# downloader.net
KiCad netlist of a schematic drawn in Altium Designer
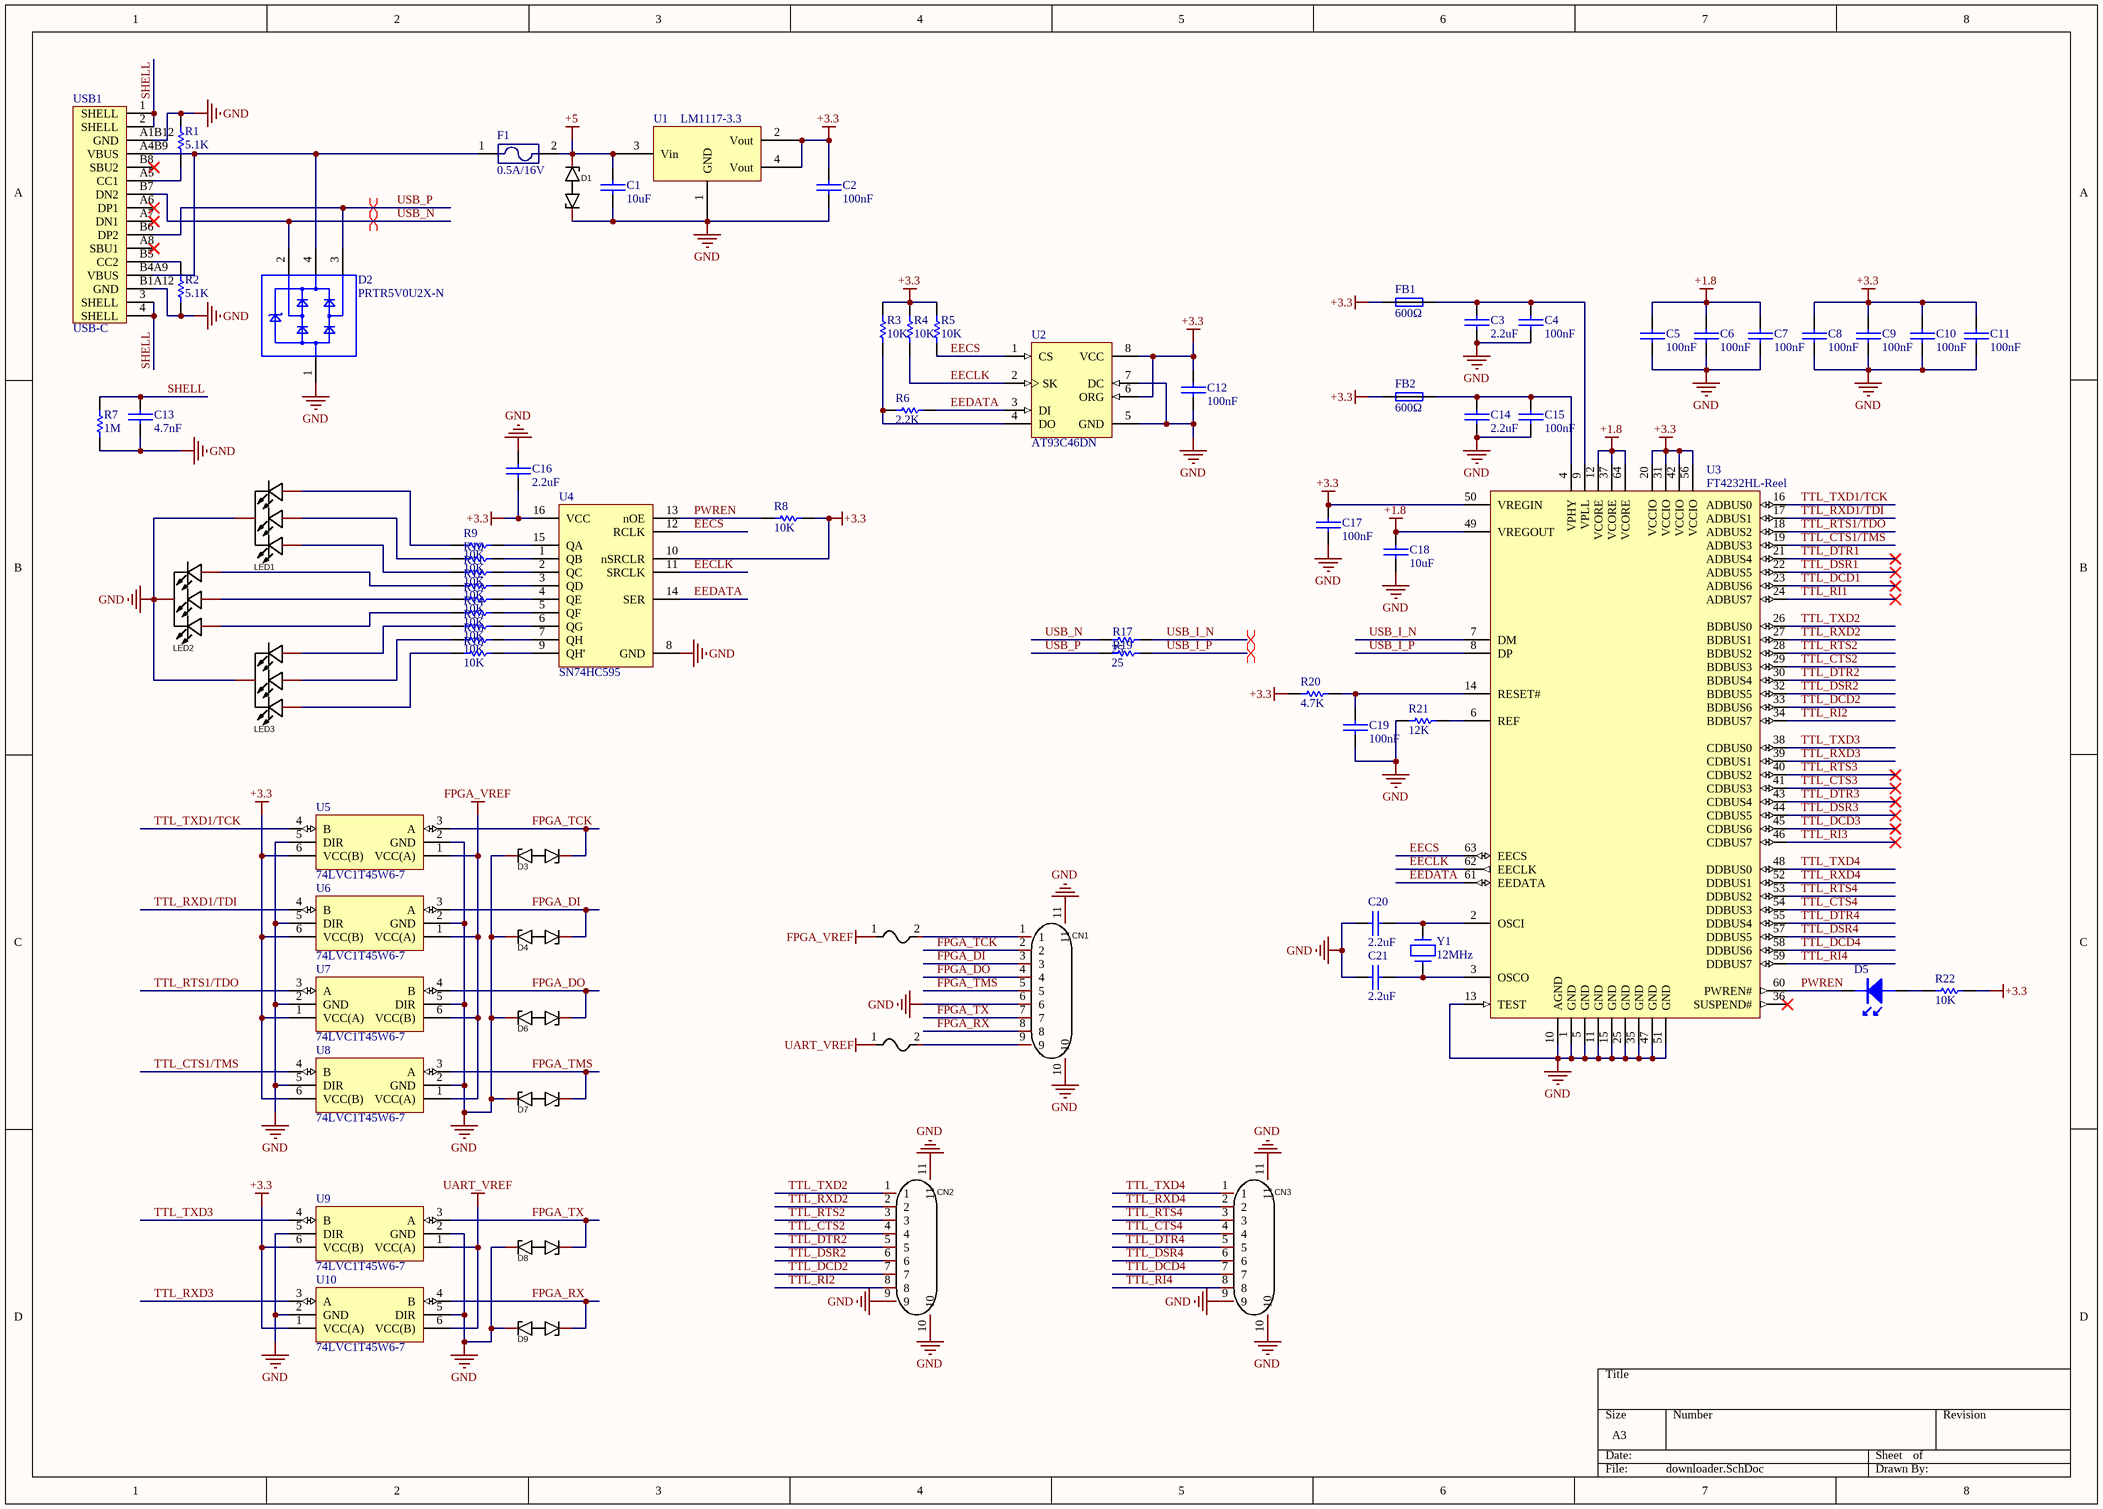
[diagram p0: downloader.SchDoc]

(export (version "E")
  (design (tool "Eeschema 10.0.6"))
  (components
    (comp (ref "C1") (value "10uF") (footprint "CAP-0603") (libsource (lib "downloader") (part "CAP0603")))
    (comp (ref "C2") (value "100nF") (footprint "CAP-0603") (libsource (lib "downloader") (part "CAP0603")))
    (comp (ref "C3") (value "2.2uF") (footprint "CAP-0603") (libsource (lib "downloader") (part "CAP0603")))
    (comp (ref "C4") (value "100nF") (footprint "CAP-0603") (libsource (lib "downloader") (part "CAP0603")))
    (comp (ref "C5") (value "100nF") (footprint "CAP-0603") (libsource (lib "downloader") (part "CAP0603")))
    (comp (ref "C6") (value "100nF") (footprint "CAP-0603") (libsource (lib "downloader") (part "CAP0603")))
    (comp (ref "C7") (value "100nF") (footprint "CAP-0603") (libsource (lib "downloader") (part "CAP0603")))
    (comp (ref "C8") (value "100nF") (footprint "CAP-0603") (libsource (lib "downloader") (part "CAP0603")))
    (comp (ref "C9") (value "100nF") (footprint "CAP-0603") (libsource (lib "downloader") (part "CAP0603")))
    (comp (ref "C10") (value "100nF") (footprint "CAP-0603") (libsource (lib "downloader") (part "CAP0603")))
    (comp (ref "C11") (value "100nF") (footprint "CAP-0603") (libsource (lib "downloader") (part "CAP0603")))
    (comp (ref "C12") (value "100nF") (footprint "CAP-0603") (libsource (lib "downloader") (part "CAP0603")))
    (comp (ref "C13") (value "4.7nF") (footprint "CAP-0603") (libsource (lib "downloader") (part "CAP-0603")))
    (comp (ref "C14") (value "2.2uF") (footprint "CAP-0603") (libsource (lib "downloader") (part "CAP0603")))
    (comp (ref "C15") (value "100nF") (footprint "CAP-0603") (libsource (lib "downloader") (part "CAP0603")))
    (comp (ref "C16") (value "2.2uF") (footprint "CAP-0603") (libsource (lib "downloader") (part "CAP-0603")))
    (comp (ref "C17") (value "100nF") (footprint "CAP-0603") (libsource (lib "downloader") (part "CAP0603")))
    (comp (ref "C18") (value "10uF") (footprint "CAP-0603") (libsource (lib "downloader") (part "CAP0603")))
    (comp (ref "C19") (value "100nF") (footprint "CAP-0603") (libsource (lib "downloader") (part "CAP-0603")))
    (comp (ref "C20") (value "2.2uF") (footprint "CAP-0603") (libsource (lib "downloader") (part "CAP-0603")))
    (comp (ref "C21") (value "2.2uF") (footprint "CAP-0603") (libsource (lib "downloader") (part "CAP-0603")))
    (comp (ref "CN1")
      (value "1.25-9PWT")
      (footprint "CONN-SMD_1.25-9PWT")
      (fields (field (name "MANUFACTURER") "FG(富港)"))
      (libsource (lib "downloader") (part "1.25-9PWT"))
    )
    (comp (ref "CN2")
      (value "1.25-9PWT")
      (footprint "CONN-SMD_1.25-9PWT")
      (fields (field (name "MANUFACTURER") "FG(富港)"))
      (libsource (lib "downloader") (part "1.25-9PWT"))
    )
    (comp (ref "CN3")
      (value "1.25-9PWT")
      (footprint "CONN-SMD_1.25-9PWT")
      (fields (field (name "MANUFACTURER") "FG(富港)"))
      (libsource (lib "downloader") (part "1.25-9PWT"))
    )
    (comp (ref "D1")
      (value "PESD5V0S1BA,115")
      (footprint "SOD-323")
      (description "115")
      (fields (field (name "MANUFACTURER") "Nexperia(安世)"))
      (libsource (lib "downloader") (part "PESD5V0S1BA"))
    )
    (comp (ref "D2")
      (value "PRTR5V0U2X-N")
      (footprint "SOT-143")
      (description "USB2.0-ESD")
      (libsource (lib "downloader") (part "PRTR5V0U2X-N"))
    )
    (comp (ref "D3")
      (value "PESD5V0S1BA,115")
      (footprint "SOD-323")
      (description "115")
      (fields (field (name "MANUFACTURER") "Nexperia(安世)"))
      (libsource (lib "downloader") (part "PESD5V0S1BA"))
    )
    (comp (ref "D4")
      (value "PESD5V0S1BA,115")
      (footprint "SOD-323")
      (description "115")
      (fields (field (name "MANUFACTURER") "Nexperia(安世)"))
      (libsource (lib "downloader") (part "PESD5V0S1BA"))
    )
    (comp (ref "D5") (value "~") (footprint "LED-0603") (libsource (lib "downloader") (part "LED-0603")))
    (comp (ref "D6")
      (value "PESD5V0S1BA,115")
      (footprint "SOD-323")
      (description "115")
      (fields (field (name "MANUFACTURER") "Nexperia(安世)"))
      (libsource (lib "downloader") (part "PESD5V0S1BA"))
    )
    (comp (ref "D7")
      (value "PESD5V0S1BA,115")
      (footprint "SOD-323")
      (description "115")
      (fields (field (name "MANUFACTURER") "Nexperia(安世)"))
      (libsource (lib "downloader") (part "PESD5V0S1BA"))
    )
    (comp (ref "D8")
      (value "PESD5V0S1BA,115")
      (footprint "SOD-323")
      (description "115")
      (fields (field (name "MANUFACTURER") "Nexperia(安世)"))
      (libsource (lib "downloader") (part "PESD5V0S1BA"))
    )
    (comp (ref "D9")
      (value "PESD5V0S1BA,115")
      (footprint "SOD-323")
      (description "115")
      (fields (field (name "MANUFACTURER") "Nexperia(安世)"))
      (libsource (lib "downloader") (part "PESD5V0S1BA"))
    )
    (comp (ref "F1") (value "0.5A/16V") (footprint "F-1206") (libsource (lib "downloader") (part "RE-FUSE")))
    (comp (ref "F2")
      (value "BSMD0805-050-6V")
      (footprint "F-0805")
      (description "050-6V")
      (fields (field (name "MANUFACTURER") "BHFUSE(佰宏)"))
      (libsource (lib "downloader") (part "BSMD0805"))
    )
    (comp (ref "F3")
      (value "BSMD0805-050-6V")
      (footprint "F-0805")
      (description "050-6V")
      (fields (field (name "MANUFACTURER") "BHFUSE(佰宏)"))
      (libsource (lib "downloader") (part "BSMD0805"))
    )
    (comp (ref "FB1") (value "600Ω") (footprint "FB-0603") (libsource (lib "downloader") (part "FB0603")))
    (comp (ref "FB2") (value "600Ω") (footprint "FB-0603") (libsource (lib "downloader") (part "FB0603")))
    (comp (ref "LED1")
      (value "TJ-S1615CY6TGLCCSRGB-A5")
      (footprint "LED-SMD_4P")
      (fields (field (name "MANUFACTURER") "TOGIALED(统佳)"))
      (libsource (lib "downloader") (part "TJ-S1615CY6TGLCCSRGB-A5"))
    )
    (comp (ref "LED2")
      (value "TJ-S1615CY6TGLCCSRGB-A5")
      (footprint "LED-SMD_4P")
      (fields (field (name "MANUFACTURER") "TOGIALED(统佳)"))
      (libsource (lib "downloader") (part "TJ-S1615CY6TGLCCSRGB-A5"))
    )
    (comp (ref "LED3")
      (value "TJ-S1615CY6TGLCCSRGB-A5")
      (footprint "LED-SMD_4P")
      (fields (field (name "MANUFACTURER") "TOGIALED(统佳)"))
      (libsource (lib "downloader") (part "TJ-S1615CY6TGLCCSRGB-A5"))
    )
    (comp (ref "R1") (value "5.1K") (footprint "RES-0603") (libsource (lib "downloader") (part "RES-0603")))
    (comp (ref "R2") (value "5.1K") (footprint "RES-0603") (libsource (lib "downloader") (part "RES-0603")))
    (comp (ref "R3") (value "10K") (footprint "RES-0603") (libsource (lib "downloader") (part "RES-0603")))
    (comp (ref "R4") (value "10K") (footprint "RES-0603") (libsource (lib "downloader") (part "RES-0603")))
    (comp (ref "R5") (value "10K") (footprint "RES-0603") (libsource (lib "downloader") (part "RES-0603")))
    (comp (ref "R6") (value "2.2K") (footprint "RES-0603") (libsource (lib "downloader") (part "RES-0603")))
    (comp (ref "R7") (value "1M") (footprint "RES-0603") (libsource (lib "downloader") (part "RES-0603")))
    (comp (ref "R8") (value "10K") (footprint "RES-0603") (libsource (lib "downloader") (part "RES-0603")))
    (comp (ref "R9") (value "10K") (footprint "RES-0603") (libsource (lib "downloader") (part "RES-0603")))
    (comp (ref "R10") (value "10K") (footprint "RES-0603") (libsource (lib "downloader") (part "RES-0603")))
    (comp (ref "R11") (value "10K") (footprint "RES-0603") (libsource (lib "downloader") (part "RES-0603")))
    (comp (ref "R12") (value "10K") (footprint "RES-0603") (libsource (lib "downloader") (part "RES-0603")))
    (comp (ref "R13") (value "10K") (footprint "RES-0603") (libsource (lib "downloader") (part "RES-0603")))
    (comp (ref "R14") (value "10K") (footprint "RES-0603") (libsource (lib "downloader") (part "RES-0603")))
    (comp (ref "R15") (value "10K") (footprint "RES-0603") (libsource (lib "downloader") (part "RES-0603")))
    (comp (ref "R16") (value "10K") (footprint "RES-0603") (libsource (lib "downloader") (part "RES-0603")))
    (comp (ref "R17") (value "25") (footprint "RES-0603") (libsource (lib "downloader") (part "RES-0603")))
    (comp (ref "R18") (value "10K") (footprint "RES-0603") (libsource (lib "downloader") (part "RES-0603")))
    (comp (ref "R19") (value "25") (footprint "RES-0603") (libsource (lib "downloader") (part "RES-0603")))
    (comp (ref "R20") (value "4.7K") (footprint "RES-0603") (libsource (lib "downloader") (part "RES-0603")))
    (comp (ref "R21") (value "12K") (footprint "RES-0603") (libsource (lib "downloader") (part "RES-0603")))
    (comp (ref "R22") (value "10K") (footprint "RES-0603") (libsource (lib "downloader") (part "RES-0603")))
    (comp (ref "U1")
      (value "LM1117-3.3")
      (footprint "SOT-223")
      (description "LDO")
      (libsource (lib "downloader") (part "LM1117-3.3"))
    )
    (comp (ref "U2") (value "AT93C46DN") (footprint "SO-8") (libsource (lib "downloader") (part "AT93C46DN")))
    (comp (ref "U3")
      (value "FT4232HL-Reel")
      (footprint "LQFP-64")
      (description "Quad High Speed USB To Multipurpose UART/MPSSE IC, LQFP-64, Tape and Reel")
      (fields (field (name "PUBLISHER") "Altium Limited"))
      (libsource (lib "downloader") (part "FT4232HL-Reel"))
    )
    (comp (ref "U4")
      (value "SN74HC595")
      (footprint "SO-16")
      (libsource (lib "downloader") (part "SN74HC595"))
    )
    (comp (ref "U5")
      (value "74LVC1T45W6-7")
      (footprint "SOT-23-6")
      (libsource (lib "downloader") (part "74LVC1T45W6-7"))
    )
    (comp (ref "U6")
      (value "74LVC1T45W6-7")
      (footprint "SOT-23-6")
      (libsource (lib "downloader") (part "74LVC1T45W6-7"))
    )
    (comp (ref "U7")
      (value "74LVC1T45W6-7")
      (footprint "SOT-23-6")
      (libsource (lib "") (part "74LVC1T45W6-7_1"))
    )
    (comp (ref "U8")
      (value "74LVC1T45W6-7")
      (footprint "SOT-23-6")
      (libsource (lib "downloader") (part "74LVC1T45W6-7"))
    )
    (comp (ref "U9")
      (value "74LVC1T45W6-7")
      (footprint "SOT-23-6")
      (libsource (lib "downloader") (part "74LVC1T45W6-7"))
    )
    (comp (ref "U10")
      (value "74LVC1T45W6-7")
      (footprint "SOT-23-6")
      (libsource (lib "") (part "74LVC1T45W6-7_1"))
    )
    (comp (ref "USB1")
      (value "USB-C")
      (footprint "USB-C")
      (description "16P")
      (libsource (lib "downloader") (part "USB-C-16P"))
    )
    (comp (ref "Y1")
      (value "12MHz")
      (footprint "XTAL-49/S_N")
      (libsource (lib "downloader") (part "XTAL-49/S_N"))
    )
  )
  (nets
    (net (code "1") (name "+1.8") (class "Default")
      (node (ref "C18") (pin "2") (pinfunction "2_2") (pintype "passive"))
      (node (ref "C5") (pin "2") (pinfunction "2_2") (pintype "passive"))
      (node (ref "C6") (pin "2") (pinfunction "2_2") (pintype "passive"))
      (node (ref "C7") (pin "2") (pinfunction "2_2") (pintype "passive"))
      (node (ref "U3") (pin "12") (pinfunction "VCORE_12") (pintype "power_in"))
      (node (ref "U3") (pin "37") (pinfunction "VCORE_37") (pintype "power_in"))
      (node (ref "U3") (pin "49") (pinfunction "VREGOUT_49") (pintype "power_in"))
      (node (ref "U3") (pin "64") (pinfunction "VCORE_64") (pintype "power_in"))
    )
    (net (code "2") (name "+3.3") (class "Default")
      (node (ref "C10") (pin "2") (pinfunction "2_2") (pintype "passive"))
      (node (ref "C11") (pin "2") (pinfunction "2_2") (pintype "passive"))
      (node (ref "C12") (pin "2") (pinfunction "2_2") (pintype "passive"))
      (node (ref "C16") (pin "2") (pinfunction "2_2") (pintype "passive"))
      (node (ref "C17") (pin "2") (pinfunction "2_2") (pintype "passive"))
      (node (ref "C2") (pin "2") (pinfunction "2_2") (pintype "passive"))
      (node (ref "C8") (pin "2") (pinfunction "2_2") (pintype "passive"))
      (node (ref "C9") (pin "2") (pinfunction "2_2") (pintype "passive"))
      (node (ref "FB1") (pin "1") (pinfunction "1_1") (pintype "passive"))
      (node (ref "FB2") (pin "1") (pinfunction "1_1") (pintype "passive"))
      (node (ref "R20") (pin "1") (pinfunction "1_1") (pintype "passive"))
      (node (ref "R22") (pin "2") (pinfunction "2_2") (pintype "passive"))
      (node (ref "R3") (pin "1") (pinfunction "1_1") (pintype "passive"))
      (node (ref "R4") (pin "1") (pinfunction "1_1") (pintype "passive"))
      (node (ref "R5") (pin "1") (pinfunction "1_1") (pintype "passive"))
      (node (ref "R8") (pin "2") (pinfunction "2_2") (pintype "passive"))
      (node (ref "U1") (pin "2") (pinfunction "Vout_2") (pintype "passive"))
      (node (ref "U1") (pin "4") (pinfunction "Vout_4") (pintype "passive"))
      (node (ref "U10") (pin "1") (pinfunction "VCC(A)_1") (pintype "power_in"))
      (node (ref "U2") (pin "6") (pinfunction "ORG_6") (pintype "input"))
      (node (ref "U2") (pin "8") (pinfunction "VCC_8") (pintype "power_in"))
      (node (ref "U3") (pin "20") (pinfunction "VCCIO_20") (pintype "power_in"))
      (node (ref "U3") (pin "31") (pinfunction "VCCIO_31") (pintype "power_in"))
      (node (ref "U3") (pin "42") (pinfunction "VCCIO_42") (pintype "power_in"))
      (node (ref "U3") (pin "50") (pinfunction "VREGIN_50") (pintype "power_in"))
      (node (ref "U3") (pin "56") (pinfunction "VCCIO_56") (pintype "power_in"))
      (node (ref "U4") (pin "10") (pinfunction "nSRCLR_10") (pintype "passive"))
      (node (ref "U4") (pin "16") (pinfunction "VCC_16") (pintype "passive"))
      (node (ref "U5") (pin "6") (pinfunction "VCC(B)_6") (pintype "power_in"))
      (node (ref "U6") (pin "6") (pinfunction "VCC(B)_6") (pintype "power_in"))
      (node (ref "U7") (pin "1") (pinfunction "VCC(A)_1") (pintype "power_in"))
      (node (ref "U8") (pin "6") (pinfunction "VCC(B)_6") (pintype "power_in"))
      (node (ref "U9") (pin "6") (pinfunction "VCC(B)_6") (pintype "power_in"))
    )
    (net (code "3") (name "+5") (class "Default")
      (node (ref "C1") (pin "2") (pinfunction "2_2") (pintype "passive"))
      (node (ref "D1") (pin "2") (pinfunction "2_2") (pintype "passive"))
      (node (ref "F1") (pin "2") (pinfunction "2_2") (pintype "passive"))
      (node (ref "U1") (pin "3") (pinfunction "Vin_3") (pintype "power_in"))
    )
    (net (code "4") (name "/EECLK") (class "Default")
      (node (ref "R4") (pin "2") (pinfunction "2_2") (pintype "passive"))
      (node (ref "U2") (pin "2") (pinfunction "SK_2") (pintype "input"))
      (node (ref "U3") (pin "62") (pinfunction "EECLK_62") (pintype "output"))
      (node (ref "U4") (pin "11") (pinfunction "SRCLK_11") (pintype "passive"))
    )
    (net (code "5") (name "/EECS") (class "Default")
      (node (ref "R5") (pin "2") (pinfunction "2_2") (pintype "passive"))
      (node (ref "U2") (pin "1") (pinfunction "CS_1") (pintype "input"))
      (node (ref "U3") (pin "63") (pinfunction "EECS_63") (pintype "bidirectional"))
      (node (ref "U4") (pin "12") (pinfunction "RCLK_12") (pintype "passive"))
    )
    (net (code "6") (name "/EEDATA") (class "Default")
      (node (ref "R6") (pin "2") (pinfunction "2_2") (pintype "passive"))
      (node (ref "U2") (pin "3") (pinfunction "DI_3") (pintype "input"))
      (node (ref "U3") (pin "61") (pinfunction "EEDATA_61") (pintype "bidirectional"))
      (node (ref "U4") (pin "14") (pinfunction "SER_14") (pintype "passive"))
    )
    (net (code "7") (name "/FPGA_DI") (class "Default")
      (node (ref "CN1") (pin "3") (pinfunction "3_3") (pintype "passive"))
      (node (ref "D4") (pin "2") (pinfunction "2_2") (pintype "passive"))
      (node (ref "U6") (pin "3") (pinfunction "A_3") (pintype "bidirectional"))
    )
    (net (code "8") (name "/FPGA_DO") (class "Default")
      (node (ref "CN1") (pin "4") (pinfunction "4_4") (pintype "passive"))
      (node (ref "D6") (pin "2") (pinfunction "2_2") (pintype "passive"))
      (node (ref "U7") (pin "4") (pinfunction "B_4") (pintype "bidirectional"))
    )
    (net (code "9") (name "/FPGA_RX") (class "Default")
      (node (ref "CN1") (pin "8") (pinfunction "8_8") (pintype "passive"))
      (node (ref "D9") (pin "2") (pinfunction "2_2") (pintype "passive"))
      (node (ref "U10") (pin "4") (pinfunction "B_4") (pintype "bidirectional"))
    )
    (net (code "10") (name "/FPGA_TCK") (class "Default")
      (node (ref "CN1") (pin "2") (pinfunction "2_2") (pintype "passive"))
      (node (ref "D3") (pin "2") (pinfunction "2_2") (pintype "passive"))
      (node (ref "U5") (pin "3") (pinfunction "A_3") (pintype "bidirectional"))
    )
    (net (code "11") (name "/FPGA_TMS") (class "Default")
      (node (ref "CN1") (pin "5") (pinfunction "5_5") (pintype "passive"))
      (node (ref "D7") (pin "2") (pinfunction "2_2") (pintype "passive"))
      (node (ref "U8") (pin "3") (pinfunction "A_3") (pintype "bidirectional"))
    )
    (net (code "12") (name "/FPGA_TX") (class "Default")
      (node (ref "CN1") (pin "7") (pinfunction "7_7") (pintype "passive"))
      (node (ref "D8") (pin "2") (pinfunction "2_2") (pintype "passive"))
      (node (ref "U9") (pin "3") (pinfunction "A_3") (pintype "bidirectional"))
    )
    (net (code "13") (name "/PWREN") (class "Default")
      (node (ref "D5") (pin "1") (pinfunction "1_1") (pintype "passive"))
      (node (ref "R8") (pin "1") (pinfunction "1_1") (pintype "passive"))
      (node (ref "U3") (pin "60") (pinfunction "PWREN#_60") (pintype "output"))
      (node (ref "U4") (pin "13") (pinfunction "nOE_13") (pintype "passive"))
    )
    (net (code "14") (name "/SHELL") (class "Default")
      (node (ref "C13") (pin "2") (pinfunction "2_2") (pintype "passive"))
      (node (ref "R7") (pin "2") (pinfunction "2_2") (pintype "passive"))
      (node (ref "USB1") (pin "1") (pinfunction "SHELL_1") (pintype "power_in"))
      (node (ref "USB1") (pin "2") (pinfunction "SHELL_2") (pintype "power_in"))
      (node (ref "USB1") (pin "3") (pinfunction "SHELL_3") (pintype "power_in"))
      (node (ref "USB1") (pin "4") (pinfunction "SHELL_4") (pintype "power_in"))
    )
    (net (code "15") (name "/TTL_CTS1{slash}TMS") (class "Default")
      (node (ref "U3") (pin "19") (pinfunction "ADBUS3_19") (pintype "bidirectional"))
      (node (ref "U8") (pin "4") (pinfunction "B_4") (pintype "bidirectional"))
    )
    (net (code "16") (name "/TTL_CTS2") (class "Default")
      (node (ref "CN2") (pin "4") (pinfunction "4_4") (pintype "passive"))
      (node (ref "U3") (pin "29") (pinfunction "BDBUS3_29") (pintype "bidirectional"))
    )
    (net (code "17") (name "/TTL_CTS3") (class "Default")
      (node (ref "U3") (pin "41") (pinfunction "CDBUS3_41") (pintype "bidirectional+no_connect"))
    )
    (net (code "18") (name "/TTL_CTS4") (class "Default")
      (node (ref "CN3") (pin "4") (pinfunction "4_4") (pintype "passive"))
      (node (ref "U3") (pin "54") (pinfunction "DDBUS3_54") (pintype "bidirectional"))
    )
    (net (code "19") (name "/TTL_DCD1") (class "Default")
      (node (ref "U3") (pin "23") (pinfunction "ADBUS6_23") (pintype "bidirectional+no_connect"))
    )
    (net (code "20") (name "/TTL_DCD2") (class "Default")
      (node (ref "CN2") (pin "7") (pinfunction "7_7") (pintype "passive"))
      (node (ref "U3") (pin "33") (pinfunction "BDBUS6_33") (pintype "bidirectional"))
    )
    (net (code "21") (name "/TTL_DCD3") (class "Default")
      (node (ref "U3") (pin "45") (pinfunction "CDBUS6_45") (pintype "bidirectional+no_connect"))
    )
    (net (code "22") (name "/TTL_DCD4") (class "Default")
      (node (ref "CN3") (pin "7") (pinfunction "7_7") (pintype "passive"))
      (node (ref "U3") (pin "58") (pinfunction "DDBUS6_58") (pintype "bidirectional"))
    )
    (net (code "23") (name "/TTL_DSR1") (class "Default")
      (node (ref "U3") (pin "22") (pinfunction "ADBUS5_22") (pintype "bidirectional+no_connect"))
    )
    (net (code "24") (name "/TTL_DSR2") (class "Default")
      (node (ref "CN2") (pin "6") (pinfunction "6_6") (pintype "passive"))
      (node (ref "U3") (pin "32") (pinfunction "BDBUS5_32") (pintype "bidirectional"))
    )
    (net (code "25") (name "/TTL_DSR3") (class "Default")
      (node (ref "U3") (pin "44") (pinfunction "CDBUS5_44") (pintype "bidirectional+no_connect"))
    )
    (net (code "26") (name "/TTL_DSR4") (class "Default")
      (node (ref "CN3") (pin "6") (pinfunction "6_6") (pintype "passive"))
      (node (ref "U3") (pin "57") (pinfunction "DDBUS5_57") (pintype "bidirectional"))
    )
    (net (code "27") (name "/TTL_DTR1") (class "Default")
      (node (ref "U3") (pin "21") (pinfunction "ADBUS4_21") (pintype "bidirectional+no_connect"))
    )
    (net (code "28") (name "/TTL_DTR2") (class "Default")
      (node (ref "CN2") (pin "5") (pinfunction "5_5") (pintype "passive"))
      (node (ref "U3") (pin "30") (pinfunction "BDBUS4_30") (pintype "bidirectional"))
    )
    (net (code "29") (name "/TTL_DTR3") (class "Default")
      (node (ref "U3") (pin "43") (pinfunction "CDBUS4_43") (pintype "bidirectional+no_connect"))
    )
    (net (code "30") (name "/TTL_DTR4") (class "Default")
      (node (ref "CN3") (pin "5") (pinfunction "5_5") (pintype "passive"))
      (node (ref "U3") (pin "55") (pinfunction "DDBUS4_55") (pintype "bidirectional"))
    )
    (net (code "31") (name "/TTL_RI1") (class "Default")
      (node (ref "U3") (pin "24") (pinfunction "ADBUS7_24") (pintype "bidirectional+no_connect"))
    )
    (net (code "32") (name "/TTL_RI2") (class "Default")
      (node (ref "CN2") (pin "8") (pinfunction "8_8") (pintype "passive"))
      (node (ref "U3") (pin "34") (pinfunction "BDBUS7_34") (pintype "bidirectional"))
    )
    (net (code "33") (name "/TTL_RI3") (class "Default")
      (node (ref "U3") (pin "46") (pinfunction "CDBUS7_46") (pintype "bidirectional+no_connect"))
    )
    (net (code "34") (name "/TTL_RI4") (class "Default")
      (node (ref "CN3") (pin "8") (pinfunction "8_8") (pintype "passive"))
      (node (ref "U3") (pin "59") (pinfunction "DDBUS7_59") (pintype "bidirectional"))
    )
    (net (code "35") (name "/TTL_RTS1{slash}TDO") (class "Default")
      (node (ref "U3") (pin "18") (pinfunction "ADBUS2_18") (pintype "bidirectional"))
      (node (ref "U7") (pin "3") (pinfunction "A_3") (pintype "bidirectional"))
    )
    (net (code "36") (name "/TTL_RTS2") (class "Default")
      (node (ref "CN2") (pin "3") (pinfunction "3_3") (pintype "passive"))
      (node (ref "U3") (pin "28") (pinfunction "BDBUS2_28") (pintype "bidirectional"))
    )
    (net (code "37") (name "/TTL_RTS3") (class "Default")
      (node (ref "U3") (pin "40") (pinfunction "CDBUS2_40") (pintype "bidirectional+no_connect"))
    )
    (net (code "38") (name "/TTL_RTS4") (class "Default")
      (node (ref "CN3") (pin "3") (pinfunction "3_3") (pintype "passive"))
      (node (ref "U3") (pin "53") (pinfunction "DDBUS2_53") (pintype "bidirectional"))
    )
    (net (code "39") (name "/TTL_RXD1{slash}TDI") (class "Default")
      (node (ref "U3") (pin "17") (pinfunction "ADBUS1_17") (pintype "bidirectional"))
      (node (ref "U6") (pin "4") (pinfunction "B_4") (pintype "bidirectional"))
    )
    (net (code "40") (name "/TTL_RXD2") (class "Default")
      (node (ref "CN2") (pin "2") (pinfunction "2_2") (pintype "passive"))
      (node (ref "U3") (pin "27") (pinfunction "BDBUS1_27") (pintype "bidirectional"))
    )
    (net (code "41") (name "/TTL_RXD3") (class "Default")
      (node (ref "U10") (pin "3") (pinfunction "A_3") (pintype "bidirectional"))
      (node (ref "U3") (pin "39") (pinfunction "CDBUS1_39") (pintype "bidirectional"))
    )
    (net (code "42") (name "/TTL_RXD4") (class "Default")
      (node (ref "CN3") (pin "2") (pinfunction "2_2") (pintype "passive"))
      (node (ref "U3") (pin "52") (pinfunction "DDBUS1_52") (pintype "bidirectional"))
    )
    (net (code "43") (name "/TTL_TXD1{slash}TCK") (class "Default")
      (node (ref "U3") (pin "16") (pinfunction "ADBUS0_16") (pintype "bidirectional"))
      (node (ref "U5") (pin "4") (pinfunction "B_4") (pintype "bidirectional"))
    )
    (net (code "44") (name "/TTL_TXD2") (class "Default")
      (node (ref "CN2") (pin "1") (pinfunction "1_1") (pintype "passive"))
      (node (ref "U3") (pin "26") (pinfunction "BDBUS0_26") (pintype "bidirectional"))
    )
    (net (code "45") (name "/TTL_TXD3") (class "Default")
      (node (ref "U3") (pin "38") (pinfunction "CDBUS0_38") (pintype "bidirectional"))
      (node (ref "U9") (pin "4") (pinfunction "B_4") (pintype "bidirectional"))
    )
    (net (code "46") (name "/TTL_TXD4") (class "Default")
      (node (ref "CN3") (pin "1") (pinfunction "1_1") (pintype "passive"))
      (node (ref "U3") (pin "48") (pinfunction "DDBUS0_48") (pintype "bidirectional"))
    )
    (net (code "47") (name "/USB_I_N") (class "Default")
      (node (ref "R17") (pin "2") (pinfunction "2_2") (pintype "passive"))
      (node (ref "U3") (pin "7") (pinfunction "DM_7") (pintype "passive"))
    )
    (net (code "48") (name "/USB_I_P") (class "Default")
      (node (ref "R19") (pin "2") (pinfunction "2_2") (pintype "passive"))
      (node (ref "U3") (pin "8") (pinfunction "DP_8") (pintype "passive"))
    )
    (net (code "49") (name "/USB_N") (class "Default")
      (node (ref "D2") (pin "2") (pinfunction "2_2") (pintype "passive"))
      (node (ref "R17") (pin "1") (pinfunction "1_1") (pintype "passive"))
      (node (ref "USB1") (pin "B7") (pinfunction "DN2_B7") (pintype "power_in"))
    )
    (net (code "50") (name "/USB_P") (class "Default")
      (node (ref "D2") (pin "3") (pinfunction "3_3") (pintype "passive"))
      (node (ref "R19") (pin "1") (pinfunction "1_1") (pintype "passive"))
      (node (ref "USB1") (pin "B6") (pinfunction "DP2_B6") (pintype "power_in"))
    )
    (net (code "51") (name "FPGA_VREF") (class "Default")
      (node (ref "F2") (pin "1") (pinfunction "1_1") (pintype "passive"))
      (node (ref "U5") (pin "1") (pinfunction "VCC(A)_1") (pintype "power_in"))
      (node (ref "U6") (pin "1") (pinfunction "VCC(A)_1") (pintype "power_in"))
      (node (ref "U7") (pin "6") (pinfunction "VCC(B)_6") (pintype "power_in"))
      (node (ref "U8") (pin "1") (pinfunction "VCC(A)_1") (pintype "power_in"))
    )
    (net (code "52") (name "GND") (class "Default")
      (node (ref "C1") (pin "1") (pinfunction "1_1") (pintype "passive"))
      (node (ref "C10") (pin "1") (pinfunction "1_1") (pintype "passive"))
      (node (ref "C11") (pin "1") (pinfunction "1_1") (pintype "passive"))
      (node (ref "C12") (pin "1") (pinfunction "1_1") (pintype "passive"))
      (node (ref "C13") (pin "1") (pinfunction "1_1") (pintype "passive"))
      (node (ref "C14") (pin "1") (pinfunction "1_1") (pintype "passive"))
      (node (ref "C15") (pin "1") (pinfunction "1_1") (pintype "passive"))
      (node (ref "C16") (pin "1") (pinfunction "1_1") (pintype "passive"))
      (node (ref "C17") (pin "1") (pinfunction "1_1") (pintype "passive"))
      (node (ref "C18") (pin "1") (pinfunction "1_1") (pintype "passive"))
      (node (ref "C19") (pin "1") (pinfunction "1_1") (pintype "passive"))
      (node (ref "C2") (pin "1") (pinfunction "1_1") (pintype "passive"))
      (node (ref "C20") (pin "1") (pinfunction "1_1") (pintype "passive"))
      (node (ref "C21") (pin "1") (pinfunction "1_1") (pintype "passive"))
      (node (ref "C3") (pin "1") (pinfunction "1_1") (pintype "passive"))
      (node (ref "C4") (pin "1") (pinfunction "1_1") (pintype "passive"))
      (node (ref "C5") (pin "1") (pinfunction "1_1") (pintype "passive"))
      (node (ref "C6") (pin "1") (pinfunction "1_1") (pintype "passive"))
      (node (ref "C7") (pin "1") (pinfunction "1_1") (pintype "passive"))
      (node (ref "C8") (pin "1") (pinfunction "1_1") (pintype "passive"))
      (node (ref "C9") (pin "1") (pinfunction "1_1") (pintype "passive"))
      (node (ref "CN1") (pin "10") (pinfunction "10_10") (pintype "passive"))
      (node (ref "CN1") (pin "11") (pinfunction "11_11") (pintype "passive"))
      (node (ref "CN1") (pin "6") (pinfunction "6_6") (pintype "passive"))
      (node (ref "CN2") (pin "10") (pinfunction "10_10") (pintype "passive"))
      (node (ref "CN2") (pin "11") (pinfunction "11_11") (pintype "passive"))
      (node (ref "CN2") (pin "9") (pinfunction "9_9") (pintype "passive"))
      (node (ref "CN3") (pin "10") (pinfunction "10_10") (pintype "passive"))
      (node (ref "CN3") (pin "11") (pinfunction "11_11") (pintype "passive"))
      (node (ref "CN3") (pin "9") (pinfunction "9_9") (pintype "passive"))
      (node (ref "D1") (pin "1") (pinfunction "1_1") (pintype "passive"))
      (node (ref "D2") (pin "1") (pinfunction "1_1") (pintype "passive"))
      (node (ref "D3") (pin "1") (pinfunction "1_1") (pintype "passive"))
      (node (ref "D4") (pin "1") (pinfunction "1_1") (pintype "passive"))
      (node (ref "D6") (pin "1") (pinfunction "1_1") (pintype "passive"))
      (node (ref "D7") (pin "1") (pinfunction "1_1") (pintype "passive"))
      (node (ref "D8") (pin "1") (pinfunction "1_1") (pintype "passive"))
      (node (ref "D9") (pin "1") (pinfunction "1_1") (pintype "passive"))
      (node (ref "LED1") (pin "1") (pinfunction "C_1") (pintype "passive"))
      (node (ref "LED2") (pin "1") (pinfunction "C_1") (pintype "passive"))
      (node (ref "LED3") (pin "1") (pinfunction "C_1") (pintype "passive"))
      (node (ref "R1") (pin "2") (pinfunction "2_2") (pintype "passive"))
      (node (ref "R2") (pin "1") (pinfunction "1_1") (pintype "passive"))
      (node (ref "R21") (pin "1") (pinfunction "1_1") (pintype "passive"))
      (node (ref "R7") (pin "1") (pinfunction "1_1") (pintype "passive"))
      (node (ref "U1") (pin "1") (pinfunction "GND_1") (pintype "passive"))
      (node (ref "U10") (pin "2") (pinfunction "GND_2") (pintype "power_in"))
      (node (ref "U10") (pin "5") (pinfunction "DIR_5") (pintype "power_in"))
      (node (ref "U2") (pin "5") (pinfunction "GND_5") (pintype "power_in"))
      (node (ref "U2") (pin "7") (pinfunction "DC_7") (pintype "input"))
      (node (ref "U3") (pin "1") (pinfunction "GND_1") (pintype "power_in"))
      (node (ref "U3") (pin "10") (pinfunction "AGND_10") (pintype "power_in"))
      (node (ref "U3") (pin "11") (pinfunction "GND_11") (pintype "power_in"))
      (node (ref "U3") (pin "13") (pinfunction "TEST_13") (pintype "input"))
      (node (ref "U3") (pin "15") (pinfunction "GND_15") (pintype "power_in"))
      (node (ref "U3") (pin "25") (pinfunction "GND_25") (pintype "power_in"))
      (node (ref "U3") (pin "35") (pinfunction "GND_35") (pintype "power_in"))
      (node (ref "U3") (pin "47") (pinfunction "GND_47") (pintype "power_in"))
      (node (ref "U3") (pin "5") (pinfunction "GND_5") (pintype "power_in"))
      (node (ref "U3") (pin "51") (pinfunction "GND_51") (pintype "power_in"))
      (node (ref "U4") (pin "8") (pinfunction "GND_8") (pintype "passive"))
      (node (ref "U5") (pin "2") (pinfunction "GND_2") (pintype "power_in"))
      (node (ref "U5") (pin "5") (pinfunction "DIR_5") (pintype "power_in"))
      (node (ref "U6") (pin "2") (pinfunction "GND_2") (pintype "power_in"))
      (node (ref "U6") (pin "5") (pinfunction "DIR_5") (pintype "power_in"))
      (node (ref "U7") (pin "2") (pinfunction "GND_2") (pintype "power_in"))
      (node (ref "U7") (pin "5") (pinfunction "DIR_5") (pintype "power_in"))
      (node (ref "U8") (pin "2") (pinfunction "GND_2") (pintype "power_in"))
      (node (ref "U8") (pin "5") (pinfunction "DIR_5") (pintype "power_in"))
      (node (ref "U9") (pin "2") (pinfunction "GND_2") (pintype "power_in"))
      (node (ref "U9") (pin "5") (pinfunction "DIR_5") (pintype "power_in"))
      (node (ref "USB1") (pin "A1B12") (pinfunction "GND_A1B12") (pintype "power_in"))
      (node (ref "USB1") (pin "B1A12") (pinfunction "GND_B1A12") (pintype "power_in"))
    )
    (net (code "53") (name "Net-(CN1-Pad1)") (class "Default")
      (node (ref "CN1") (pin "1") (pinfunction "1_1") (pintype "passive"))
      (node (ref "F2") (pin "2") (pinfunction "2_2") (pintype "passive"))
    )
    (net (code "54") (name "Net-(CN1-Pad9)") (class "Default")
      (node (ref "CN1") (pin "9") (pinfunction "9_9") (pintype "passive"))
      (node (ref "F3") (pin "2") (pinfunction "2_2") (pintype "passive"))
    )
    (net (code "55") (name "Net-(D2-Pad4)") (class "Default")
      (node (ref "D2") (pin "4") (pinfunction "4_4") (pintype "passive"))
      (node (ref "F1") (pin "1") (pinfunction "1_1") (pintype "passive"))
      (node (ref "USB1") (pin "A4B9") (pinfunction "VBUS_A4B9") (pintype "power_in"))
      (node (ref "USB1") (pin "B4A9") (pinfunction "VBUS_B4A9") (pintype "power_in"))
    )
    (net (code "56") (name "Net-(D5-Pad2)") (class "Default")
      (node (ref "D5") (pin "2") (pinfunction "2_2") (pintype "passive"))
      (node (ref "R22") (pin "1") (pinfunction "1_1") (pintype "passive"))
    )
    (net (code "57") (name "Net-(LED1-B)") (class "Default")
      (node (ref "LED1") (pin "2") (pinfunction "B_2") (pintype "passive"))
      (node (ref "R11") (pin "1") (pinfunction "1_1") (pintype "passive"))
    )
    (net (code "58") (name "Net-(LED1-G)") (class "Default")
      (node (ref "LED1") (pin "3") (pinfunction "G_3") (pintype "passive"))
      (node (ref "R10") (pin "1") (pinfunction "1_1") (pintype "passive"))
    )
    (net (code "59") (name "Net-(LED1-R)") (class "Default")
      (node (ref "LED1") (pin "4") (pinfunction "R_4") (pintype "passive"))
      (node (ref "R9") (pin "1") (pinfunction "1_1") (pintype "passive"))
    )
    (net (code "60") (name "Net-(LED2-B)") (class "Default")
      (node (ref "LED2") (pin "2") (pinfunction "B_2") (pintype "passive"))
      (node (ref "R14") (pin "1") (pinfunction "1_1") (pintype "passive"))
    )
    (net (code "61") (name "Net-(LED2-G)") (class "Default")
      (node (ref "LED2") (pin "3") (pinfunction "G_3") (pintype "passive"))
      (node (ref "R13") (pin "1") (pinfunction "1_1") (pintype "passive"))
    )
    (net (code "62") (name "Net-(LED2-R)") (class "Default")
      (node (ref "LED2") (pin "4") (pinfunction "R_4") (pintype "passive"))
      (node (ref "R12") (pin "1") (pinfunction "1_1") (pintype "passive"))
    )
    (net (code "63") (name "Net-(LED3-B)") (class "Default")
      (node (ref "LED3") (pin "2") (pinfunction "B_2") (pintype "passive"))
      (node (ref "R18") (pin "1") (pinfunction "1_1") (pintype "passive"))
    )
    (net (code "64") (name "Net-(LED3-G)") (class "Default")
      (node (ref "LED3") (pin "3") (pinfunction "G_3") (pintype "passive"))
      (node (ref "R16") (pin "1") (pinfunction "1_1") (pintype "passive"))
    )
    (net (code "65") (name "Net-(LED3-R)") (class "Default")
      (node (ref "LED3") (pin "4") (pinfunction "R_4") (pintype "passive"))
      (node (ref "R15") (pin "1") (pinfunction "1_1") (pintype "passive"))
    )
    (net (code "66") (name "Net-(U2-DO)") (class "Default")
      (node (ref "R3") (pin "2") (pinfunction "2_2") (pintype "passive"))
      (node (ref "R6") (pin "1") (pinfunction "1_1") (pintype "passive"))
      (node (ref "U2") (pin "4") (pinfunction "DO_4") (pintype "tri_state"))
    )
    (net (code "67") (name "Net-(U3-OSCI)") (class "Default")
      (node (ref "C20") (pin "2") (pinfunction "2_2") (pintype "passive"))
      (node (ref "U3") (pin "2") (pinfunction "OSCI_2") (pintype "passive"))
      (node (ref "Y1") (pin "2") (pinfunction "2_2") (pintype "passive"))
    )
    (net (code "68") (name "Net-(U3-OSCO)") (class "Default")
      (node (ref "C21") (pin "2") (pinfunction "2_2") (pintype "passive"))
      (node (ref "U3") (pin "3") (pinfunction "OSCO_3") (pintype "passive"))
      (node (ref "Y1") (pin "1") (pinfunction "1_1") (pintype "passive"))
    )
    (net (code "69") (name "Net-(U3-REF)") (class "Default")
      (node (ref "R21") (pin "2") (pinfunction "2_2") (pintype "passive"))
      (node (ref "U3") (pin "6") (pinfunction "REF_6") (pintype "passive"))
    )
    (net (code "70") (name "Net-(U3-RESET#)") (class "Default")
      (node (ref "C19") (pin "2") (pinfunction "2_2") (pintype "passive"))
      (node (ref "R20") (pin "2") (pinfunction "2_2") (pintype "passive"))
      (node (ref "U3") (pin "14") (pinfunction "RESET#_14") (pintype "passive"))
    )
    (net (code "71") (name "Net-(U3-VPHY)") (class "Default")
      (node (ref "C14") (pin "2") (pinfunction "2_2") (pintype "passive"))
      (node (ref "C15") (pin "2") (pinfunction "2_2") (pintype "passive"))
      (node (ref "FB2") (pin "2") (pinfunction "2_2") (pintype "passive"))
      (node (ref "U3") (pin "4") (pinfunction "VPHY_4") (pintype "power_in"))
    )
    (net (code "72") (name "Net-(U3-VPLL)") (class "Default")
      (node (ref "C3") (pin "2") (pinfunction "2_2") (pintype "passive"))
      (node (ref "C4") (pin "2") (pinfunction "2_2") (pintype "passive"))
      (node (ref "FB1") (pin "2") (pinfunction "2_2") (pintype "passive"))
      (node (ref "U3") (pin "9") (pinfunction "VPLL_9") (pintype "power_in"))
    )
    (net (code "73") (name "Net-(U4-QA)") (class "Default")
      (node (ref "R9") (pin "2") (pinfunction "2_2") (pintype "passive"))
      (node (ref "U4") (pin "15") (pinfunction "QA_15") (pintype "passive"))
    )
    (net (code "74") (name "Net-(U4-QB)") (class "Default")
      (node (ref "R10") (pin "2") (pinfunction "2_2") (pintype "passive"))
      (node (ref "U4") (pin "1") (pinfunction "QB_1") (pintype "passive"))
    )
    (net (code "75") (name "Net-(U4-QC)") (class "Default")
      (node (ref "R11") (pin "2") (pinfunction "2_2") (pintype "passive"))
      (node (ref "U4") (pin "2") (pinfunction "QC_2") (pintype "passive"))
    )
    (net (code "76") (name "Net-(U4-QD)") (class "Default")
      (node (ref "R12") (pin "2") (pinfunction "2_2") (pintype "passive"))
      (node (ref "U4") (pin "3") (pinfunction "QD_3") (pintype "passive"))
    )
    (net (code "77") (name "Net-(U4-QE)") (class "Default")
      (node (ref "R13") (pin "2") (pinfunction "2_2") (pintype "passive"))
      (node (ref "U4") (pin "4") (pinfunction "QE_4") (pintype "passive"))
    )
    (net (code "78") (name "Net-(U4-QF)") (class "Default")
      (node (ref "R14") (pin "2") (pinfunction "2_2") (pintype "passive"))
      (node (ref "U4") (pin "5") (pinfunction "QF_5") (pintype "passive"))
    )
    (net (code "79") (name "Net-(U4-QG)") (class "Default")
      (node (ref "R15") (pin "2") (pinfunction "2_2") (pintype "passive"))
      (node (ref "U4") (pin "6") (pinfunction "QG_6") (pintype "passive"))
    )
    (net (code "80") (name "Net-(U4-QH')") (class "Default")
      (node (ref "R18") (pin "2") (pinfunction "2_2") (pintype "passive"))
      (node (ref "U4") (pin "9") (pinfunction "QH'_9") (pintype "passive"))
    )
    (net (code "81") (name "Net-(U4-QH)") (class "Default")
      (node (ref "R16") (pin "2") (pinfunction "2_2") (pintype "passive"))
      (node (ref "U4") (pin "7") (pinfunction "QH_7") (pintype "passive"))
    )
    (net (code "82") (name "Net-(USB1-CC1)") (class "Default")
      (node (ref "R1") (pin "1") (pinfunction "1_1") (pintype "passive"))
      (node (ref "USB1") (pin "A5") (pinfunction "CC1_A5") (pintype "power_in"))
    )
    (net (code "83") (name "Net-(USB1-CC2)") (class "Default")
      (node (ref "R2") (pin "2") (pinfunction "2_2") (pintype "passive"))
      (node (ref "USB1") (pin "B5") (pinfunction "CC2_B5") (pintype "power_in"))
    )
    (net (code "84") (name "UART_VREF") (class "Default")
      (node (ref "F3") (pin "1") (pinfunction "1_1") (pintype "passive"))
      (node (ref "U10") (pin "6") (pinfunction "VCC(B)_6") (pintype "power_in"))
      (node (ref "U9") (pin "1") (pinfunction "VCC(A)_1") (pintype "power_in"))
    )
    (net (code "85") (name "unconnected-(U3-SUSPEND#-Pad36)") (class "Default")
      (node (ref "U3") (pin "36") (pinfunction "SUSPEND#_36") (pintype "output+no_connect"))
    )
    (net (code "86") (name "unconnected-(USB1-DN1-PadA7)") (class "Default")
      (node (ref "USB1") (pin "A7") (pinfunction "DN1_A7") (pintype "power_in+no_connect"))
    )
    (net (code "87") (name "unconnected-(USB1-DP1-PadA6)") (class "Default")
      (node (ref "USB1") (pin "A6") (pinfunction "DP1_A6") (pintype "power_in+no_connect"))
    )
    (net (code "88") (name "unconnected-(USB1-SBU1-PadA8)") (class "Default")
      (node (ref "USB1") (pin "A8") (pinfunction "SBU1_A8") (pintype "power_in+no_connect"))
    )
    (net (code "89") (name "unconnected-(USB1-SBU2-PadB8)") (class "Default")
      (node (ref "USB1") (pin "B8") (pinfunction "SBU2_B8") (pintype "power_in+no_connect"))
    )
  )
)
